# MOSFET_breakout.net
KiCad netlist of a schematic drawn in EAGLE
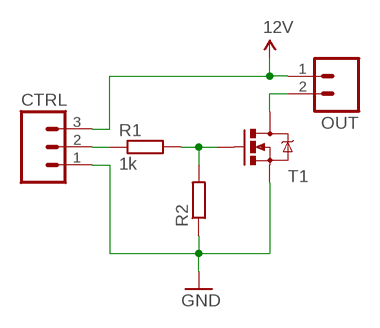
[diagram p0: schematic, sheet 1]

(export (version "E")
  (design (tool "Eeschema 10.0.6"))
  (components
    (comp (ref "CTRL")
      (value "M03PTH")
      (footprint "eagle-import:1X03")
      (libsource (lib "eagle-import") (part "M03PTH"))
    )
    (comp (ref "OUT")
      (value "M02PTH")
      (footprint "eagle-import:1X02")
      (libsource (lib "eagle-import") (part "M02PTH"))
    )
    (comp (ref "R1")
      (value "1k")
      (footprint "eagle-import:R603")
      (libsource (lib "eagle-import") (part "RESISTOR-0603"))
    )
    (comp (ref "R2")
      (value "RESISTOR-0603")
      (footprint "eagle-import:R603")
      (libsource (lib "eagle-import") (part "RESISTOR-0603"))
    )
    (comp (ref "T1")
      (value "MOSFET-NCHANNELFDD8780")
      (footprint "eagle-import:DPAK")
      (libsource (lib "eagle-import") (part "MOSFET-NCHANNELFDD8780"))
    )
  )
  (nets
    (net (code "1") (name "12V") (class "Default")
      (node (ref "CTRL") (pin "3") (pinfunction "3_3") (pintype "passive"))
      (node (ref "OUT") (pin "1") (pinfunction "1_1") (pintype "passive"))
    )
    (net (code "2") (name "GND") (class "Default")
      (node (ref "CTRL") (pin "1") (pinfunction "1_1") (pintype "passive"))
      (node (ref "R2") (pin "1") (pinfunction "1_1") (pintype "passive"))
      (node (ref "T1") (pin "3") (pinfunction "S_3") (pintype "passive"))
    )
    (net (code "3") (name "Net-(CTRL-Pad2)") (class "Default")
      (node (ref "CTRL") (pin "2") (pinfunction "2_2") (pintype "passive"))
      (node (ref "R1") (pin "1") (pinfunction "1_1") (pintype "passive"))
    )
    (net (code "4") (name "Net-(T1-D)") (class "Default")
      (node (ref "OUT") (pin "2") (pinfunction "2_2") (pintype "passive"))
      (node (ref "T1") (pin "4") (pinfunction "D_4") (pintype "passive"))
    )
    (net (code "5") (name "Net-(T1-G)") (class "Default")
      (node (ref "R1") (pin "2") (pinfunction "2_2") (pintype "passive"))
      (node (ref "R2") (pin "2") (pinfunction "2_2") (pintype "passive"))
      (node (ref "T1") (pin "1") (pinfunction "G_1") (pintype "passive"))
    )
  )
)
